# Environment-ArduinoNano44-Mini-Enclosure.net
KiCad netlist of a schematic drawn in EAGLE
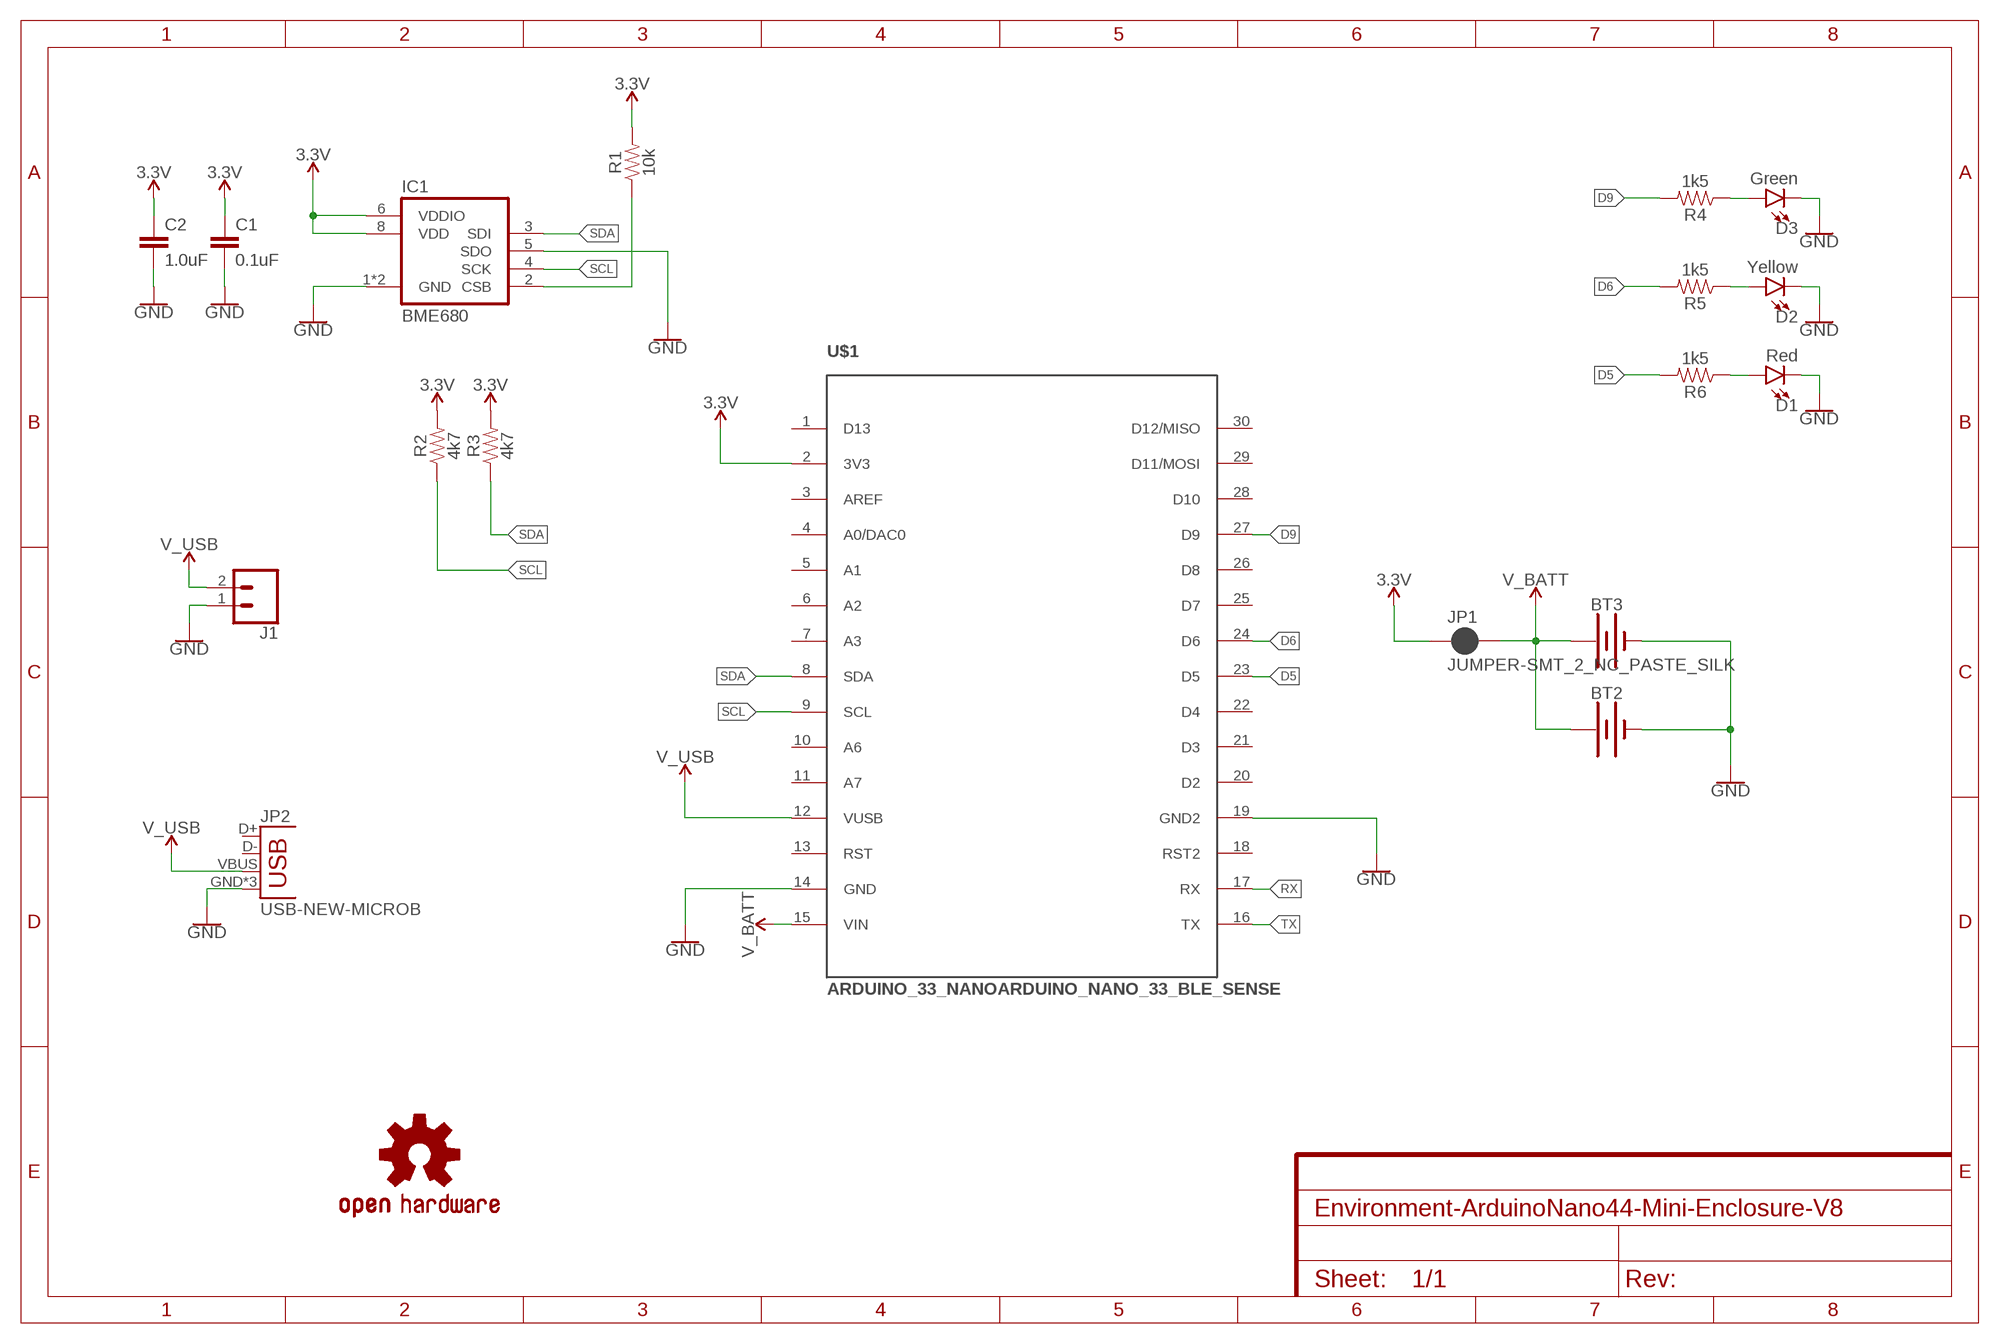
[diagram p0: schematic, sheet 1]

(export (version "E")
  (design (tool "Eeschema 10.0.6"))
  (components
    (comp (ref "BT2")
      (value "BATTERY-12MM_PTH")
      (footprint "eagle-import:BATTCON_12MM_PTH")
      (libsource (lib "eagle-import") (part "BATTERY-12MM_PTH"))
    )
    (comp (ref "BT3")
      (value "BATTERY-12MM_PTH")
      (footprint "eagle-import:BATTCON_12MM_PTH")
      (libsource (lib "eagle-import") (part "BATTERY-12MM_PTH"))
    )
    (comp (ref "C1")
      (value "0.1uF")
      (footprint "eagle-import:0805")
      (libsource (lib "eagle-import") (part "0.1UF-0805-25V"))
    )
    (comp (ref "C2")
      (value "1.0uF")
      (footprint "eagle-import:0805")
      (libsource (lib "eagle-import") (part "1.0UF-0805-25V-10%"))
    )
    (comp (ref "D1")
      (value "Red")
      (footprint "eagle-import:LED-1206")
      (libsource (lib "eagle-import") (part "LED1206"))
    )
    (comp (ref "D2")
      (value "Yellow")
      (footprint "eagle-import:LED-1206")
      (libsource (lib "eagle-import") (part "LED1206"))
    )
    (comp (ref "D3")
      (value "Green")
      (footprint "eagle-import:LED-1206")
      (libsource (lib "eagle-import") (part "LED1206"))
    )
    (comp (ref "IC1")
      (value "BME680")
      (footprint "eagle-import:BME680")
      (libsource (lib "eagle-import") (part "BME680"))
    )
    (comp (ref "J1")
      (value "CONN_02JST-2-PH-SIDE")
      (footprint "eagle-import:JST-2-SMD")
      (libsource (lib "eagle-import") (part "CONN_02JST-2-PH-SIDE"))
    )
    (comp (ref "JP1")
      (value "JUMPER-SMT_2_NC_PASTE_SILK")
      (footprint "eagle-import:SMT-JUMPER_2_NC_PASTE_SILK")
      (libsource (lib "eagle-import") (part "JUMPER-SMT_2_NC_PASTE_SILK"))
    )
    (comp (ref "JP2")
      (value "USB-NEW-MICROB")
      (footprint "eagle-import:USB-MICROB")
      (libsource (lib "eagle-import") (part "USB-NEW-MICROB"))
    )
    (comp (ref "LOGO1")
      (value "OSHW-LOGOM")
      (footprint "eagle-import:OSHW-LOGO-M")
      (libsource (lib "eagle-import") (part "OSHW-LOGOM"))
    )
    (comp (ref "R1")
      (value "10k")
      (footprint "eagle-import:0805")
      (libsource (lib "eagle-import") (part "RESISTOR0805"))
    )
    (comp (ref "R2")
      (value "4k7")
      (footprint "eagle-import:0805")
      (libsource (lib "eagle-import") (part "RESISTOR0805"))
    )
    (comp (ref "R3")
      (value "4k7")
      (footprint "eagle-import:0805")
      (libsource (lib "eagle-import") (part "RESISTOR0805"))
    )
    (comp (ref "R4")
      (value "1k5")
      (footprint "eagle-import:0805")
      (libsource (lib "eagle-import") (part "RESISTOR0805"))
    )
    (comp (ref "R5")
      (value "1k5")
      (footprint "eagle-import:0805")
      (libsource (lib "eagle-import") (part "RESISTOR0805"))
    )
    (comp (ref "R6")
      (value "1k5")
      (footprint "eagle-import:0805")
      (libsource (lib "eagle-import") (part "RESISTOR0805"))
    )
    (comp (ref "U$1")
      (value "ARDUINO_33_NANOARDUINO_NANO_33_BLE_SENSE")
      (footprint "eagle-import:ARDUINO_NANO_33")
      (libsource (lib "eagle-import") (part "ARDUINO_33_NANOARDUINO_NANO_33_BLE_SENSE"))
    )
  )
  (nets
    (net (code "1") (name "3.3V") (class "Default")
      (node (ref "C1") (pin "1") (pinfunction "1_1") (pintype "passive"))
      (node (ref "C2") (pin "1") (pinfunction "1_1") (pintype "passive"))
      (node (ref "IC1") (pin "6") (pinfunction "VDDIO_6") (pintype "power_in"))
      (node (ref "IC1") (pin "8") (pinfunction "VDD_8") (pintype "power_in"))
      (node (ref "JP1") (pin "1") (pinfunction "1_1") (pintype "passive"))
      (node (ref "R1") (pin "2") (pinfunction "2_2") (pintype "passive"))
      (node (ref "R2") (pin "2") (pinfunction "2_2") (pintype "passive"))
      (node (ref "R3") (pin "2") (pinfunction "2_2") (pintype "passive"))
      (node (ref "U$1") (pin "2") (pinfunction "3V3_2") (pintype "power_in"))
    )
    (net (code "2") (name "D5") (class "Default")
      (node (ref "R6") (pin "2") (pinfunction "2_2") (pintype "passive"))
      (node (ref "U$1") (pin "23") (pinfunction "D5_23") (pintype "bidirectional"))
    )
    (net (code "3") (name "D6") (class "Default")
      (node (ref "R5") (pin "2") (pinfunction "2_2") (pintype "passive"))
      (node (ref "U$1") (pin "24") (pinfunction "D6_24") (pintype "bidirectional"))
    )
    (net (code "4") (name "D9") (class "Default")
      (node (ref "R4") (pin "2") (pinfunction "2_2") (pintype "passive"))
      (node (ref "U$1") (pin "27") (pinfunction "D9_27") (pintype "bidirectional"))
    )
    (net (code "5") (name "GND") (class "Default")
      (node (ref "BT2") (pin "GND") (pinfunction "-_GND") (pintype "power_in"))
      (node (ref "BT3") (pin "GND") (pinfunction "-_GND") (pintype "power_in"))
      (node (ref "C1") (pin "2") (pinfunction "2_2") (pintype "passive"))
      (node (ref "C2") (pin "2") (pinfunction "2_2") (pintype "passive"))
      (node (ref "D1") (pin "C") (pinfunction "C_C") (pintype "passive"))
      (node (ref "D2") (pin "C") (pinfunction "C_C") (pintype "passive"))
      (node (ref "D3") (pin "C") (pinfunction "C_C") (pintype "passive"))
      (node (ref "IC1") (pin "1") (pinfunction "GND_1") (pintype "power_in"))
      (node (ref "IC1") (pin "5") (pinfunction "SDO_5") (pintype "output"))
      (node (ref "IC1") (pin "7") (pinfunction "GND_7") (pintype "power_in"))
      (node (ref "J1") (pin "1") (pinfunction "2_1") (pintype "passive"))
      (node (ref "JP2") (pin "GND") (pinfunction "GND_GND") (pintype "bidirectional"))
      (node (ref "JP2") (pin "MT1") (pinfunction "GND_MT1") (pintype "bidirectional"))
      (node (ref "JP2") (pin "MT2") (pinfunction "GND_MT2") (pintype "bidirectional"))
      (node (ref "U$1") (pin "14") (pinfunction "GND_14") (pintype "bidirectional"))
      (node (ref "U$1") (pin "19") (pinfunction "GND2_19") (pintype "bidirectional"))
    )
    (net (code "6") (name "Net-(D1-PadA)") (class "Default")
      (node (ref "D1") (pin "A") (pinfunction "A_A") (pintype "passive"))
      (node (ref "R6") (pin "1") (pinfunction "1_1") (pintype "passive"))
    )
    (net (code "7") (name "Net-(D2-PadA)") (class "Default")
      (node (ref "D2") (pin "A") (pinfunction "A_A") (pintype "passive"))
      (node (ref "R5") (pin "1") (pinfunction "1_1") (pintype "passive"))
    )
    (net (code "8") (name "Net-(D3-PadA)") (class "Default")
      (node (ref "D3") (pin "A") (pinfunction "A_A") (pintype "passive"))
      (node (ref "R4") (pin "1") (pinfunction "1_1") (pintype "passive"))
    )
    (net (code "9") (name "Net-(IC1-CSB)") (class "Default")
      (node (ref "IC1") (pin "2") (pinfunction "CSB_2") (pintype "input"))
      (node (ref "R1") (pin "1") (pinfunction "1_1") (pintype "passive"))
    )
    (net (code "10") (name "RX") (class "Default")
      (node (ref "U$1") (pin "17") (pinfunction "RX_17") (pintype "bidirectional"))
    )
    (net (code "11") (name "SCL") (class "Default")
      (node (ref "IC1") (pin "4") (pinfunction "SCK_4") (pintype "input"))
      (node (ref "R2") (pin "1") (pinfunction "1_1") (pintype "passive"))
      (node (ref "U$1") (pin "9") (pinfunction "SCL_9") (pintype "bidirectional"))
    )
    (net (code "12") (name "SDA") (class "Default")
      (node (ref "IC1") (pin "3") (pinfunction "SDI_3") (pintype "input"))
      (node (ref "R3") (pin "1") (pinfunction "1_1") (pintype "passive"))
      (node (ref "U$1") (pin "8") (pinfunction "SDA_8") (pintype "bidirectional"))
    )
    (net (code "13") (name "TX") (class "Default")
      (node (ref "U$1") (pin "16") (pinfunction "TX_16") (pintype "bidirectional"))
    )
    (net (code "14") (name "V_BATT") (class "Default")
      (node (ref "BT2") (pin "VCC@1") (pinfunction "+_VCC@1") (pintype "power_in"))
      (node (ref "BT3") (pin "VCC@1") (pinfunction "+_VCC@1") (pintype "power_in"))
      (node (ref "JP1") (pin "2") (pinfunction "2_2") (pintype "passive"))
      (node (ref "U$1") (pin "15") (pinfunction "VIN_15") (pintype "power_in"))
    )
    (net (code "15") (name "V_USB") (class "Default")
      (node (ref "J1") (pin "2") (pinfunction "1_2") (pintype "passive"))
      (node (ref "JP2") (pin "VBUS") (pinfunction "VBUS_VBUS") (pintype "bidirectional"))
      (node (ref "U$1") (pin "12") (pinfunction "VUSB_12") (pintype "power_in"))
    )
    (net (code "16") (name "unconnected-(JP2-PadD+)") (class "Default")
      (node (ref "JP2") (pin "D+") (pinfunction "D+_D+") (pintype "bidirectional"))
    )
    (net (code "17") (name "unconnected-(JP2-PadD-)") (class "Default")
      (node (ref "JP2") (pin "D-") (pinfunction "D-_D-") (pintype "bidirectional"))
    )
    (net (code "18") (name "unconnected-(U$1-A0{slash}DAC0-Pad4)") (class "Default")
      (node (ref "U$1") (pin "4") (pinfunction "A0/DAC0_4") (pintype "bidirectional"))
    )
    (net (code "19") (name "unconnected-(U$1-A1-Pad5)") (class "Default")
      (node (ref "U$1") (pin "5") (pinfunction "A1_5") (pintype "bidirectional"))
    )
    (net (code "20") (name "unconnected-(U$1-A2-Pad6)") (class "Default")
      (node (ref "U$1") (pin "6") (pinfunction "A2_6") (pintype "bidirectional"))
    )
    (net (code "21") (name "unconnected-(U$1-A3-Pad7)") (class "Default")
      (node (ref "U$1") (pin "7") (pinfunction "A3_7") (pintype "bidirectional"))
    )
    (net (code "22") (name "unconnected-(U$1-A6-Pad10)") (class "Default")
      (node (ref "U$1") (pin "10") (pinfunction "A6_10") (pintype "bidirectional"))
    )
    (net (code "23") (name "unconnected-(U$1-A7-Pad11)") (class "Default")
      (node (ref "U$1") (pin "11") (pinfunction "A7_11") (pintype "bidirectional"))
    )
    (net (code "24") (name "unconnected-(U$1-AREF-Pad3)") (class "Default")
      (node (ref "U$1") (pin "3") (pinfunction "AREF_3") (pintype "output"))
    )
    (net (code "25") (name "unconnected-(U$1-D2-Pad20)") (class "Default")
      (node (ref "U$1") (pin "20") (pinfunction "D2_20") (pintype "bidirectional"))
    )
    (net (code "26") (name "unconnected-(U$1-D3-Pad21)") (class "Default")
      (node (ref "U$1") (pin "21") (pinfunction "D3_21") (pintype "bidirectional"))
    )
    (net (code "27") (name "unconnected-(U$1-D4-Pad22)") (class "Default")
      (node (ref "U$1") (pin "22") (pinfunction "D4_22") (pintype "bidirectional"))
    )
    (net (code "28") (name "unconnected-(U$1-D7-Pad25)") (class "Default")
      (node (ref "U$1") (pin "25") (pinfunction "D7_25") (pintype "bidirectional"))
    )
    (net (code "29") (name "unconnected-(U$1-D8-Pad26)") (class "Default")
      (node (ref "U$1") (pin "26") (pinfunction "D8_26") (pintype "bidirectional"))
    )
    (net (code "30") (name "unconnected-(U$1-D10-Pad28)") (class "Default")
      (node (ref "U$1") (pin "28") (pinfunction "D10_28") (pintype "bidirectional"))
    )
    (net (code "31") (name "unconnected-(U$1-D11{slash}MOSI-Pad29)") (class "Default")
      (node (ref "U$1") (pin "29") (pinfunction "D11/MOSI_29") (pintype "bidirectional"))
    )
    (net (code "32") (name "unconnected-(U$1-D12{slash}MISO-Pad30)") (class "Default")
      (node (ref "U$1") (pin "30") (pinfunction "D12/MISO_30") (pintype "bidirectional"))
    )
    (net (code "33") (name "unconnected-(U$1-D13-Pad1)") (class "Default")
      (node (ref "U$1") (pin "1") (pinfunction "D13_1") (pintype "bidirectional"))
    )
    (net (code "34") (name "unconnected-(U$1-RST-Pad13)") (class "Default")
      (node (ref "U$1") (pin "13") (pinfunction "RST_13") (pintype "bidirectional"))
    )
    (net (code "35") (name "unconnected-(U$1-RST2-Pad18)") (class "Default")
      (node (ref "U$1") (pin "18") (pinfunction "RST2_18") (pintype "bidirectional"))
    )
  )
)
